# SCH_Plantcare_Module-v3_2024-10-31.net
KiCad netlist of a schematic drawn in EasyEDA
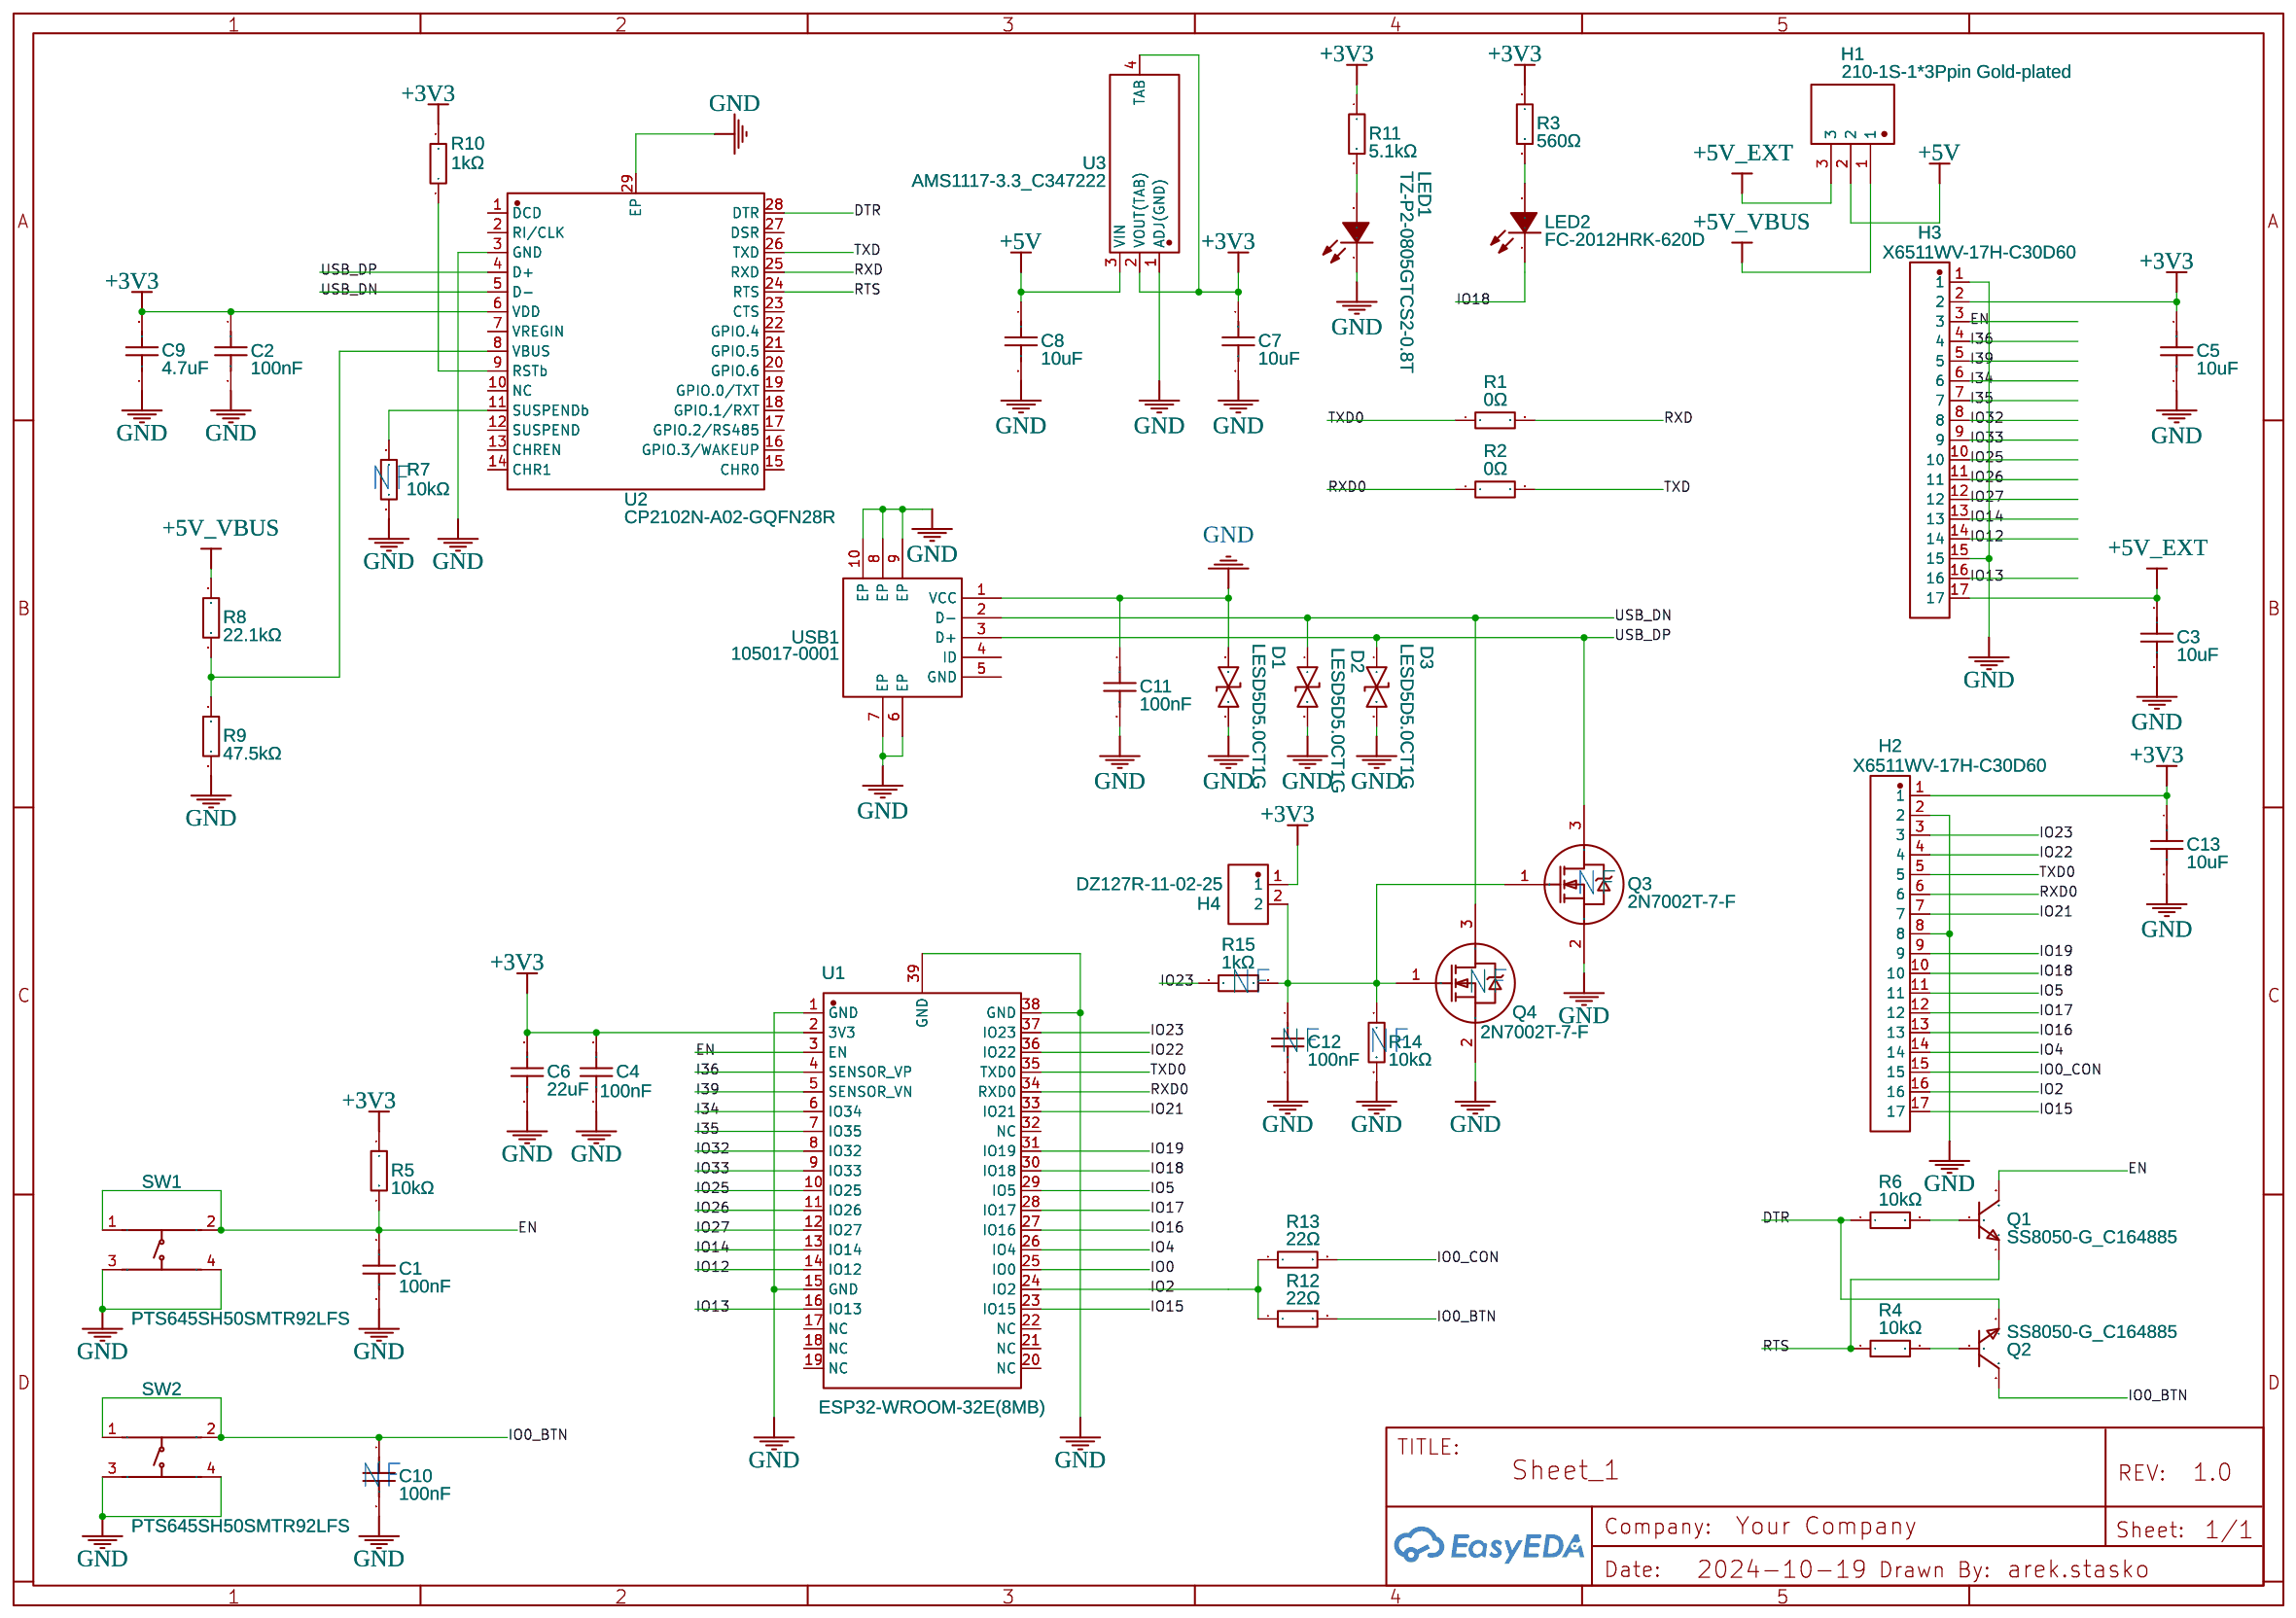
[diagram p0: schematic sheet]

(export (version "E")
  (design (tool "Eeschema 10.0.6"))
  (components
    (comp (ref "C1")
      (value "100nF")
      (fields
        (field (name "Manufacturer Part") "CL05B104KO5NNNC")
        (field (name "Manufacturer") "SAMSUNG(三星)")
      )
      (libsource (lib "") (part "CL05B104KO5NNNC"))
    )
    (comp (ref "C2")
      (value "100nF")
      (fields
        (field (name "Manufacturer Part") "CL05B104KO5NNNC")
        (field (name "Manufacturer") "SAMSUNG(三星)")
      )
      (libsource (lib "") (part "CL05B104KO5NNNC"))
    )
    (comp (ref "C3")
      (value "10uF")
      (fields
        (field (name "Manufacturer Part") "CL05A106MP5NUNC")
        (field (name "Manufacturer") "SAMSUNG(三星)")
      )
      (libsource (lib "") (part "CL05A106MP5NUNC_C315248"))
    )
    (comp (ref "C4")
      (value "100nF")
      (fields
        (field (name "Manufacturer Part") "CL05B104KO5NNNC")
        (field (name "Manufacturer") "SAMSUNG(三星)")
      )
      (libsource (lib "") (part "CL05B104KO5NNNC"))
    )
    (comp (ref "C5")
      (value "10uF")
      (fields
        (field (name "Manufacturer Part") "CL05A106MP5NUNC")
        (field (name "Manufacturer") "SAMSUNG(三星)")
      )
      (libsource (lib "") (part "CL05A106MP5NUNC_C315248"))
    )
    (comp (ref "C6")
      (value "22uF")
      (fields
        (field (name "Manufacturer Part") "CL21A226MAYNNNE")
        (field (name "Manufacturer") "SAMSUNG(三星)")
      )
      (libsource (lib "") (part "CL21A226MAYNNNE"))
    )
    (comp (ref "C7")
      (value "10uF")
      (fields
        (field (name "Manufacturer Part") "CL05A106MP5NUNC")
        (field (name "Manufacturer") "SAMSUNG(三星)")
      )
      (libsource (lib "") (part "CL05A106MP5NUNC_C315248"))
    )
    (comp (ref "C8")
      (value "10uF")
      (fields
        (field (name "Manufacturer Part") "CL05A106MP5NUNC")
        (field (name "Manufacturer") "SAMSUNG(三星)")
      )
      (libsource (lib "") (part "CL05A106MP5NUNC_C315248"))
    )
    (comp (ref "C9")
      (value "4.7uF")
      (fields
        (field (name "Manufacturer Part") "CL05A475KP5NRNC")
        (field (name "Manufacturer") "SAMSUNG(三星)")
      )
      (libsource (lib "") (part "CL05A475KP5NRNC"))
    )
    (comp (ref "C10")
      (value "100nF")
      (fields
        (field (name "Manufacturer Part") "CL05B104KO5NNNC")
        (field (name "Manufacturer") "SAMSUNG(三星)")
      )
      (libsource (lib "") (part "CL05B104KO5NNNC"))
    )
    (comp (ref "C11")
      (value "100nF")
      (fields
        (field (name "Manufacturer Part") "CL05B104KO5NNNC")
        (field (name "Manufacturer") "SAMSUNG(三星)")
      )
      (libsource (lib "") (part "CL05B104KO5NNNC"))
    )
    (comp (ref "C12")
      (value "100nF")
      (fields
        (field (name "Manufacturer Part") "CL05B104KO5NNNC")
        (field (name "Manufacturer") "SAMSUNG(三星)")
      )
      (libsource (lib "") (part "CL05B104KO5NNNC"))
    )
    (comp (ref "C13")
      (value "10uF")
      (fields
        (field (name "Manufacturer Part") "CL05A106MP5NUNC")
        (field (name "Manufacturer") "SAMSUNG(三星)")
      )
      (libsource (lib "") (part "CL05A106MP5NUNC_C315248"))
    )
    (comp (ref "D1")
      (value "LESD5D5.0CT1G")
      (fields (field (name "Manufacturer") "LRC(乐山无线电)"))
      (libsource (lib "") (part "LESD5D5.0CT1G"))
    )
    (comp (ref "D2")
      (value "LESD5D5.0CT1G")
      (fields (field (name "Manufacturer") "LRC(乐山无线电)"))
      (libsource (lib "") (part "LESD5D5.0CT1G_1"))
    )
    (comp (ref "D3")
      (value "LESD5D5.0CT1G")
      (fields (field (name "Manufacturer") "LRC(乐山无线电)"))
      (libsource (lib "") (part "LESD5D5.0CT1G_1"))
    )
    (comp (ref "H1")
      (value "210-1S-1*3Ppin Gold-plated")
      (fields (field (name "Manufacturer Part") "B-2101S03P-A110") (field (name "Manufacturer") "Ckmtw(灿科盟)"))
      (libsource (lib "") (part "210-1S-1*3Ppin Gold-plated"))
    )
    (comp (ref "H2")
      (value "X6511WV-17H-C30D60")
      (fields
        (field (name "Manufacturer Part") "X6511WV-17H-C60D30")
        (field (name "Manufacturer") "XKB Connection(中国星坤)")
      )
      (libsource (lib "") (part "X6511WV-17H-C30D60"))
    )
    (comp (ref "H3")
      (value "X6511WV-17H-C30D60")
      (fields
        (field (name "Manufacturer Part") "X6511WV-17H-C60D30")
        (field (name "Manufacturer") "XKB Connection(中国星坤)")
      )
      (libsource (lib "") (part "X6511WV-17H-C30D60"))
    )
    (comp (ref "H4")
      (value "DZ127R-11-02-25")
      (fields (field (name "Manufacturer") "DEALON(德艺隆)"))
      (libsource (lib "") (part "DZ127R-11-02-25"))
    )
    (comp (ref "LED1")
      (value "TZ-P2-0805GTCS2-0.8T")
      (fields (field (name "Manufacturer") "TUOZHAN(拓展光电)"))
      (libsource (lib "") (part "TZ-P2-0805GTCS2-0.8T"))
    )
    (comp (ref "LED2")
      (value "FC-2012HRK-620D")
      (fields (field (name "Manufacturer Part") "NCD0805R1") (field (name "Manufacturer") "国星光电"))
      (libsource (lib "") (part "FC-2012HRK-620D"))
    )
    (comp (ref "Q1")
      (value "SS8050-G_C164885")
      (fields (field (name "Manufacturer Part") "SS8050-G") (field (name "Manufacturer") "CJ(江苏长电/长晶)"))
      (libsource (lib "") (part "SS8050-G_C164885_1"))
    )
    (comp (ref "Q2")
      (value "SS8050-G_C164885")
      (fields (field (name "Manufacturer Part") "SS8050-G") (field (name "Manufacturer") "CJ(江苏长电/长晶)"))
      (libsource (lib "") (part "SS8050-G_C164885"))
    )
    (comp (ref "Q3")
      (value "2N7002T-7-F")
      (fields (field (name "Manufacturer") "DIODES(美台)"))
      (libsource (lib "") (part "2N7002T-7-F"))
    )
    (comp (ref "Q4")
      (value "2N7002T-7-F")
      (fields (field (name "Manufacturer") "DIODES(美台)"))
      (libsource (lib "") (part "2N7002T-7-F"))
    )
    (comp (ref "R1")
      (value "0Ω")
      (fields
        (field (name "Manufacturer Part") "0402WGF0000TCE")
        (field (name "Manufacturer") "UNI-ROYAL(厚声)")
      )
      (libsource (lib "") (part "0402WGF0000TCE"))
    )
    (comp (ref "R2")
      (value "0Ω")
      (fields
        (field (name "Manufacturer Part") "0402WGF0000TCE")
        (field (name "Manufacturer") "UNI-ROYAL(厚声)")
      )
      (libsource (lib "") (part "0402WGF0000TCE"))
    )
    (comp (ref "R3")
      (value "560Ω")
      (fields
        (field (name "Manufacturer Part") "0402WGF5600TCE")
        (field (name "Manufacturer") "UNI-ROYAL(厚声)")
      )
      (libsource (lib "") (part "0402WGF5600TCE"))
    )
    (comp (ref "R4")
      (value "10kΩ")
      (fields
        (field (name "Manufacturer Part") "0402WGF1002TCE")
        (field (name "Manufacturer") "UNI-ROYAL(厚声)")
      )
      (libsource (lib "") (part "0402WGF1002TCE"))
    )
    (comp (ref "R5")
      (value "10kΩ")
      (fields
        (field (name "Manufacturer Part") "0402WGF1002TCE")
        (field (name "Manufacturer") "UNI-ROYAL(厚声)")
      )
      (libsource (lib "") (part "0402WGF1002TCE_1"))
    )
    (comp (ref "R6")
      (value "10kΩ")
      (fields
        (field (name "Manufacturer Part") "0402WGF1002TCE")
        (field (name "Manufacturer") "UNI-ROYAL(厚声)")
      )
      (libsource (lib "") (part "0402WGF1002TCE"))
    )
    (comp (ref "R7")
      (value "10kΩ")
      (fields
        (field (name "Manufacturer Part") "0402WGF1002TCE")
        (field (name "Manufacturer") "UNI-ROYAL(厚声)")
      )
      (libsource (lib "") (part "0402WGF1002TCE_1"))
    )
    (comp (ref "R8")
      (value "22.1kΩ")
      (fields
        (field (name "Manufacturer Part") "0402WGF2212TCE")
        (field (name "Manufacturer") "UNI-ROYAL(厚声)")
      )
      (libsource (lib "") (part "0402WGF2212TCE"))
    )
    (comp (ref "R9")
      (value "47.5kΩ")
      (fields
        (field (name "Manufacturer Part") "0402WGF4752TCE")
        (field (name "Manufacturer") "UNI-ROYAL(厚声)")
      )
      (libsource (lib "") (part "0402WGF4752TCE"))
    )
    (comp (ref "R10")
      (value "1kΩ")
      (fields
        (field (name "Manufacturer Part") "0402WGF1001TCE")
        (field (name "Manufacturer") "UNI-ROYAL(厚声)")
      )
      (libsource (lib "") (part "0402WGF1001TCE"))
    )
    (comp (ref "R11")
      (value "5.1kΩ")
      (fields
        (field (name "Manufacturer Part") "0402WGF5101TCE")
        (field (name "Manufacturer") "UNI-ROYAL(厚声)")
      )
      (libsource (lib "") (part "0402WGF5101TCE"))
    )
    (comp (ref "R12")
      (value "22Ω")
      (fields
        (field (name "Manufacturer Part") "0402WGF220JTCE")
        (field (name "Manufacturer") "UNI-ROYAL(厚声)")
      )
      (libsource (lib "") (part "0402WGF220JTCE"))
    )
    (comp (ref "R13")
      (value "22Ω")
      (fields
        (field (name "Manufacturer Part") "0402WGF220JTCE")
        (field (name "Manufacturer") "UNI-ROYAL(厚声)")
      )
      (libsource (lib "") (part "0402WGF220JTCE"))
    )
    (comp (ref "R14")
      (value "10kΩ")
      (fields
        (field (name "Manufacturer Part") "0402WGF1002TCE")
        (field (name "Manufacturer") "UNI-ROYAL(厚声)")
      )
      (libsource (lib "") (part "0402WGF1002TCE_1"))
    )
    (comp (ref "R15")
      (value "1kΩ")
      (fields
        (field (name "Manufacturer Part") "0402WGF1001TCE")
        (field (name "Manufacturer") "UNI-ROYAL(厚声)")
      )
      (libsource (lib "") (part "0402WGF1001TCE_1"))
    )
    (comp (ref "SW1")
      (value "PTS645SH50SMTR92LFS")
      (fields (field (name "Manufacturer") "C&K"))
      (libsource (lib "") (part "PTS645SH50SMTR92LFS"))
    )
    (comp (ref "SW2")
      (value "PTS645SH50SMTR92LFS")
      (fields (field (name "Manufacturer") "C&K"))
      (libsource (lib "") (part "PTS645SH50SMTR92LFS"))
    )
    (comp (ref "U1")
      (value "ESP32-WROOM-32E(8MB)")
      (fields
        (field (name "Manufacturer Part") "ESP32-WROOM-32E-N8")
        (field (name "Manufacturer") "ESPRESSIF(乐鑫)")
      )
      (libsource (lib "") (part "ESP32-WROOM-32E(8MB)"))
    )
    (comp (ref "U2")
      (value "CP2102N-A02-GQFN28R")
      (fields (field (name "Manufacturer") "SKYWORKS/SILICON LABS(芯科)"))
      (libsource (lib "") (part "CP2102N-A02-GQFN28R"))
    )
    (comp (ref "U3")
      (value "AMS1117-3.3_C347222")
      (fields (field (name "Manufacturer Part") "AMS1117-3.3") (field (name "Manufacturer") "UMW(友台半导体)"))
      (libsource (lib "") (part "AMS1117-3.3_C347222"))
    )
    (comp (ref "USB1")
      (value "105017-0001")
      (fields (field (name "Manufacturer Part") "1050170001") (field (name "Manufacturer") "MOLEX"))
      (libsource (lib "") (part "105017-0001"))
    )
  )
  (nets
    (net (code "1") (name "+3V3") (class "Default")
      (node (ref "C13") (pin "1") (pinfunction "1_1") (pintype "unspecified"))
      (node (ref "C2") (pin "1") (pinfunction "1_1") (pintype "unspecified"))
      (node (ref "C4") (pin "1") (pinfunction "1_1") (pintype "unspecified"))
      (node (ref "C5") (pin "1") (pinfunction "1_1") (pintype "unspecified"))
      (node (ref "C6") (pin "1") (pinfunction "1_1") (pintype "unspecified"))
      (node (ref "C7") (pin "1") (pinfunction "1_1") (pintype "unspecified"))
      (node (ref "C9") (pin "2") (pinfunction "2_2") (pintype "unspecified"))
      (node (ref "H2") (pin "1") (pinfunction "1_1") (pintype "unspecified"))
      (node (ref "H3") (pin "2") (pinfunction "2_2") (pintype "unspecified"))
      (node (ref "H4") (pin "1") (pinfunction "1_1") (pintype "unspecified"))
      (node (ref "R10") (pin "2") (pinfunction "2_2") (pintype "input"))
      (node (ref "R11") (pin "1") (pinfunction "1_1") (pintype "input"))
      (node (ref "R3") (pin "1") (pinfunction "1_1") (pintype "input"))
      (node (ref "R5") (pin "1") (pinfunction "1_1") (pintype "input"))
      (node (ref "U1") (pin "2") (pinfunction "3V3_2") (pintype "unspecified"))
      (node (ref "U2") (pin "6") (pinfunction "VDD_6") (pintype "unspecified"))
      (node (ref "U3") (pin "2") (pinfunction "VOUT(TAB)_2") (pintype "unspecified"))
      (node (ref "U3") (pin "4") (pinfunction "TAB_4") (pintype "unspecified"))
    )
    (net (code "2") (name "+5V") (class "Default")
      (node (ref "C8") (pin "1") (pinfunction "1_1") (pintype "unspecified"))
      (node (ref "H1") (pin "2") (pinfunction "2_2") (pintype "unspecified"))
      (node (ref "U3") (pin "3") (pinfunction "VIN_3") (pintype "unspecified"))
    )
    (net (code "3") (name "+5V_EXT") (class "Default")
      (node (ref "C3") (pin "1") (pinfunction "1_1") (pintype "unspecified"))
      (node (ref "H1") (pin "3") (pinfunction "3_3") (pintype "unspecified"))
      (node (ref "H3") (pin "17") (pinfunction "17_17") (pintype "unspecified"))
    )
    (net (code "4") (name "+5V_VBUS") (class "Default")
      (node (ref "H1") (pin "1") (pinfunction "1_1") (pintype "unspecified"))
      (node (ref "R8") (pin "1") (pinfunction "1_1") (pintype "input"))
    )
    (net (code "5") (name "/DTR") (class "Default")
      (node (ref "Q2") (pin "2") (pinfunction "E_2") (pintype "unspecified"))
      (node (ref "R6") (pin "1") (pinfunction "1_1") (pintype "input"))
      (node (ref "U2") (pin "28") (pinfunction "DTR_28") (pintype "unspecified"))
    )
    (net (code "6") (name "/EN") (class "Default")
      (node (ref "C1") (pin "1") (pinfunction "1_1") (pintype "unspecified"))
      (node (ref "H3") (pin "3") (pinfunction "3_3") (pintype "unspecified"))
      (node (ref "Q1") (pin "3") (pinfunction "C_3") (pintype "unspecified"))
      (node (ref "R5") (pin "2") (pinfunction "2_2") (pintype "input"))
      (node (ref "SW1") (pin "1") (pinfunction "1_1") (pintype "unspecified"))
      (node (ref "SW1") (pin "2") (pinfunction "2_2") (pintype "unspecified"))
      (node (ref "U1") (pin "3") (pinfunction "EN_3") (pintype "unspecified"))
    )
    (net (code "7") (name "/I34") (class "Default")
      (node (ref "H3") (pin "6") (pinfunction "6_6") (pintype "unspecified"))
      (node (ref "U1") (pin "6") (pinfunction "IO34_6") (pintype "unspecified"))
    )
    (net (code "8") (name "/I35") (class "Default")
      (node (ref "H3") (pin "7") (pinfunction "7_7") (pintype "unspecified"))
      (node (ref "U1") (pin "7") (pinfunction "IO35_7") (pintype "unspecified"))
    )
    (net (code "9") (name "/I36") (class "Default")
      (node (ref "H3") (pin "4") (pinfunction "4_4") (pintype "unspecified"))
      (node (ref "U1") (pin "4") (pinfunction "SENSOR_VP_4") (pintype "unspecified"))
    )
    (net (code "10") (name "/I39") (class "Default")
      (node (ref "H3") (pin "5") (pinfunction "5_5") (pintype "unspecified"))
      (node (ref "U1") (pin "5") (pinfunction "SENSOR_VN_5") (pintype "unspecified"))
    )
    (net (code "11") (name "/IO0") (class "Default")
      (node (ref "U1") (pin "25") (pinfunction "IO0_25") (pintype "unspecified"))
    )
    (net (code "12") (name "/IO0_BTN") (class "Default")
      (node (ref "C10") (pin "1") (pinfunction "1_1") (pintype "unspecified"))
      (node (ref "Q2") (pin "3") (pinfunction "C_3") (pintype "unspecified"))
      (node (ref "R12") (pin "2") (pinfunction "2_2") (pintype "input"))
      (node (ref "SW2") (pin "1") (pinfunction "1_1") (pintype "unspecified"))
      (node (ref "SW2") (pin "2") (pinfunction "2_2") (pintype "unspecified"))
    )
    (net (code "13") (name "/IO0_CON") (class "Default")
      (node (ref "H2") (pin "15") (pinfunction "15_15") (pintype "unspecified"))
      (node (ref "R13") (pin "2") (pinfunction "2_2") (pintype "input"))
    )
    (net (code "14") (name "/IO2") (class "Default")
      (node (ref "H2") (pin "16") (pinfunction "16_16") (pintype "unspecified"))
      (node (ref "R12") (pin "1") (pinfunction "1_1") (pintype "input"))
      (node (ref "R13") (pin "1") (pinfunction "1_1") (pintype "input"))
      (node (ref "U1") (pin "24") (pinfunction "IO2_24") (pintype "unspecified"))
    )
    (net (code "15") (name "/IO4") (class "Default")
      (node (ref "H2") (pin "14") (pinfunction "14_14") (pintype "unspecified"))
      (node (ref "U1") (pin "26") (pinfunction "IO4_26") (pintype "unspecified"))
    )
    (net (code "16") (name "/IO5") (class "Default")
      (node (ref "H2") (pin "11") (pinfunction "11_11") (pintype "unspecified"))
      (node (ref "U1") (pin "29") (pinfunction "IO5_29") (pintype "unspecified"))
    )
    (net (code "17") (name "/IO12") (class "Default")
      (node (ref "H3") (pin "14") (pinfunction "14_14") (pintype "unspecified"))
      (node (ref "U1") (pin "14") (pinfunction "IO12_14") (pintype "unspecified"))
    )
    (net (code "18") (name "/IO13") (class "Default")
      (node (ref "H3") (pin "16") (pinfunction "16_16") (pintype "unspecified"))
      (node (ref "U1") (pin "16") (pinfunction "IO13_16") (pintype "unspecified"))
    )
    (net (code "19") (name "/IO14") (class "Default")
      (node (ref "H3") (pin "13") (pinfunction "13_13") (pintype "unspecified"))
      (node (ref "U1") (pin "13") (pinfunction "IO14_13") (pintype "unspecified"))
    )
    (net (code "20") (name "/IO15") (class "Default")
      (node (ref "H2") (pin "17") (pinfunction "17_17") (pintype "unspecified"))
      (node (ref "U1") (pin "23") (pinfunction "IO15_23") (pintype "unspecified"))
    )
    (net (code "21") (name "/IO16") (class "Default")
      (node (ref "H2") (pin "13") (pinfunction "13_13") (pintype "unspecified"))
      (node (ref "U1") (pin "27") (pinfunction "IO16_27") (pintype "unspecified"))
    )
    (net (code "22") (name "/IO17") (class "Default")
      (node (ref "H2") (pin "12") (pinfunction "12_12") (pintype "unspecified"))
      (node (ref "U1") (pin "28") (pinfunction "IO17_28") (pintype "unspecified"))
    )
    (net (code "23") (name "/IO18") (class "Default")
      (node (ref "H2") (pin "10") (pinfunction "10_10") (pintype "unspecified"))
      (node (ref "LED2") (pin "2") (pinfunction "-_2") (pintype "unspecified"))
      (node (ref "U1") (pin "30") (pinfunction "IO18_30") (pintype "unspecified"))
    )
    (net (code "24") (name "/IO19") (class "Default")
      (node (ref "H2") (pin "9") (pinfunction "9_9") (pintype "unspecified"))
      (node (ref "U1") (pin "31") (pinfunction "IO19_31") (pintype "unspecified"))
    )
    (net (code "25") (name "/IO21") (class "Default")
      (node (ref "H2") (pin "7") (pinfunction "7_7") (pintype "unspecified"))
      (node (ref "U1") (pin "33") (pinfunction "IO21_33") (pintype "unspecified"))
    )
    (net (code "26") (name "/IO22") (class "Default")
      (node (ref "H2") (pin "4") (pinfunction "4_4") (pintype "unspecified"))
      (node (ref "U1") (pin "36") (pinfunction "IO22_36") (pintype "unspecified"))
    )
    (net (code "27") (name "/IO23") (class "Default")
      (node (ref "H2") (pin "3") (pinfunction "3_3") (pintype "unspecified"))
      (node (ref "R15") (pin "1") (pinfunction "1_1") (pintype "input"))
      (node (ref "U1") (pin "37") (pinfunction "IO23_37") (pintype "unspecified"))
    )
    (net (code "28") (name "/IO25") (class "Default")
      (node (ref "H3") (pin "10") (pinfunction "10_10") (pintype "unspecified"))
      (node (ref "U1") (pin "10") (pinfunction "IO25_10") (pintype "unspecified"))
    )
    (net (code "29") (name "/IO26") (class "Default")
      (node (ref "H3") (pin "11") (pinfunction "11_11") (pintype "unspecified"))
      (node (ref "U1") (pin "11") (pinfunction "IO26_11") (pintype "unspecified"))
    )
    (net (code "30") (name "/IO27") (class "Default")
      (node (ref "H3") (pin "12") (pinfunction "12_12") (pintype "unspecified"))
      (node (ref "U1") (pin "12") (pinfunction "IO27_12") (pintype "unspecified"))
    )
    (net (code "31") (name "/IO32") (class "Default")
      (node (ref "H3") (pin "8") (pinfunction "8_8") (pintype "unspecified"))
      (node (ref "U1") (pin "8") (pinfunction "IO32_8") (pintype "unspecified"))
    )
    (net (code "32") (name "/IO33") (class "Default")
      (node (ref "H3") (pin "9") (pinfunction "9_9") (pintype "unspecified"))
      (node (ref "U1") (pin "9") (pinfunction "IO33_9") (pintype "unspecified"))
    )
    (net (code "33") (name "/RTS") (class "Default")
      (node (ref "Q1") (pin "2") (pinfunction "E_2") (pintype "unspecified"))
      (node (ref "R4") (pin "1") (pinfunction "1_1") (pintype "input"))
      (node (ref "U2") (pin "24") (pinfunction "RTS_24") (pintype "unspecified"))
    )
    (net (code "34") (name "/RXD") (class "Default")
      (node (ref "R1") (pin "2") (pinfunction "2_2") (pintype "input"))
      (node (ref "U2") (pin "25") (pinfunction "RXD_25") (pintype "unspecified"))
    )
    (net (code "35") (name "/RXD0") (class "Default")
      (node (ref "H2") (pin "6") (pinfunction "6_6") (pintype "unspecified"))
      (node (ref "R2") (pin "1") (pinfunction "1_1") (pintype "input"))
      (node (ref "U1") (pin "34") (pinfunction "RXD0_34") (pintype "unspecified"))
    )
    (net (code "36") (name "/TXD") (class "Default")
      (node (ref "R2") (pin "2") (pinfunction "2_2") (pintype "input"))
      (node (ref "U2") (pin "26") (pinfunction "TXD_26") (pintype "unspecified"))
    )
    (net (code "37") (name "/TXD0") (class "Default")
      (node (ref "H2") (pin "5") (pinfunction "5_5") (pintype "unspecified"))
      (node (ref "R1") (pin "1") (pinfunction "1_1") (pintype "input"))
      (node (ref "U1") (pin "35") (pinfunction "TXD0_35") (pintype "unspecified"))
    )
    (net (code "38") (name "/USB_DN") (class "Default")
      (node (ref "D2") (pin "1") (pinfunction "1_1") (pintype "unspecified"))
      (node (ref "Q4") (pin "3") (pinfunction "D_3") (pintype "unspecified"))
      (node (ref "U2") (pin "5") (pinfunction "D-_5") (pintype "unspecified"))
      (node (ref "USB1") (pin "2") (pinfunction "D-_2") (pintype "unspecified"))
    )
    (net (code "39") (name "/USB_DP") (class "Default")
      (node (ref "D3") (pin "1") (pinfunction "1_1") (pintype "unspecified"))
      (node (ref "Q3") (pin "3") (pinfunction "D_3") (pintype "unspecified"))
      (node (ref "U2") (pin "4") (pinfunction "D+_4") (pintype "unspecified"))
      (node (ref "USB1") (pin "3") (pinfunction "D+_3") (pintype "unspecified"))
    )
    (net (code "40") (name "GND") (class "Default")
      (node (ref "C1") (pin "2") (pinfunction "2_2") (pintype "unspecified"))
      (node (ref "C10") (pin "2") (pinfunction "2_2") (pintype "unspecified"))
      (node (ref "C11") (pin "1") (pinfunction "1_1") (pintype "unspecified"))
      (node (ref "C11") (pin "2") (pinfunction "2_2") (pintype "unspecified"))
      (node (ref "C12") (pin "2") (pinfunction "2_2") (pintype "unspecified"))
      (node (ref "C13") (pin "2") (pinfunction "2_2") (pintype "unspecified"))
      (node (ref "C2") (pin "2") (pinfunction "2_2") (pintype "unspecified"))
      (node (ref "C3") (pin "2") (pinfunction "2_2") (pintype "unspecified"))
      (node (ref "C4") (pin "2") (pinfunction "2_2") (pintype "unspecified"))
      (node (ref "C5") (pin "2") (pinfunction "2_2") (pintype "unspecified"))
      (node (ref "C6") (pin "2") (pinfunction "2_2") (pintype "unspecified"))
      (node (ref "C7") (pin "2") (pinfunction "2_2") (pintype "unspecified"))
      (node (ref "C8") (pin "2") (pinfunction "2_2") (pintype "unspecified"))
      (node (ref "C9") (pin "1") (pinfunction "1_1") (pintype "unspecified"))
      (node (ref "D1") (pin "1") (pinfunction "1_1") (pintype "unspecified"))
      (node (ref "D1") (pin "2") (pinfunction "2_2") (pintype "unspecified"))
      (node (ref "D2") (pin "2") (pinfunction "2_2") (pintype "unspecified"))
      (node (ref "D3") (pin "2") (pinfunction "2_2") (pintype "unspecified"))
      (node (ref "H2") (pin "2") (pinfunction "2_2") (pintype "unspecified"))
      (node (ref "H2") (pin "8") (pinfunction "8_8") (pintype "unspecified"))
      (node (ref "H3") (pin "1") (pinfunction "1_1") (pintype "unspecified"))
      (node (ref "H3") (pin "15") (pinfunction "15_15") (pintype "unspecified"))
      (node (ref "LED1") (pin "1") (pinfunction "-_1") (pintype "unspecified"))
      (node (ref "Q3") (pin "2") (pinfunction "S_2") (pintype "unspecified"))
      (node (ref "Q4") (pin "2") (pinfunction "S_2") (pintype "unspecified"))
      (node (ref "R14") (pin "2") (pinfunction "2_2") (pintype "input"))
      (node (ref "R7") (pin "2") (pinfunction "2_2") (pintype "input"))
      (node (ref "R9") (pin "2") (pinfunction "2_2") (pintype "input"))
      (node (ref "SW1") (pin "3") (pinfunction "3_3") (pintype "unspecified"))
      (node (ref "SW1") (pin "4") (pinfunction "4_4") (pintype "unspecified"))
      (node (ref "SW2") (pin "3") (pinfunction "3_3") (pintype "unspecified"))
      (node (ref "SW2") (pin "4") (pinfunction "4_4") (pintype "unspecified"))
      (node (ref "U1") (pin "1") (pinfunction "GND_1") (pintype "unspecified"))
      (node (ref "U1") (pin "15") (pinfunction "GND_15") (pintype "unspecified"))
      (node (ref "U1") (pin "38") (pinfunction "GND_38") (pintype "unspecified"))
      (node (ref "U1") (pin "39") (pinfunction "GND_39") (pintype "unspecified"))
      (node (ref "U2") (pin "29") (pinfunction "EP_29") (pintype "unspecified"))
      (node (ref "U2") (pin "3") (pinfunction "GND_3") (pintype "unspecified"))
      (node (ref "U3") (pin "1") (pinfunction "ADJ(GND)_1") (pintype "unspecified"))
      (node (ref "USB1") (pin "1") (pinfunction "VCC_1") (pintype "unspecified"))
      (node (ref "USB1") (pin "10") (pinfunction "EP_10") (pintype "unspecified"))
      (node (ref "USB1") (pin "6") (pinfunction "EP_6") (pintype "unspecified"))
      (node (ref "USB1") (pin "7") (pinfunction "EP_7") (pintype "unspecified"))
      (node (ref "USB1") (pin "8") (pinfunction "EP_8") (pintype "unspecified"))
      (node (ref "USB1") (pin "9") (pinfunction "EP_9") (pintype "unspecified"))
    )
    (net (code "41") (name "Net-(LED1-+)") (class "Default")
      (node (ref "LED1") (pin "2") (pinfunction "+_2") (pintype "unspecified"))
      (node (ref "R11") (pin "2") (pinfunction "2_2") (pintype "input"))
    )
    (net (code "42") (name "Net-(LED2-+)") (class "Default")
      (node (ref "LED2") (pin "1") (pinfunction "+_1") (pintype "unspecified"))
      (node (ref "R3") (pin "2") (pinfunction "2_2") (pintype "input"))
    )
    (net (code "43") (name "Net-(Q1-B)") (class "Default")
      (node (ref "Q1") (pin "1") (pinfunction "B_1") (pintype "unspecified"))
      (node (ref "R6") (pin "2") (pinfunction "2_2") (pintype "input"))
    )
    (net (code "44") (name "Net-(Q2-B)") (class "Default")
      (node (ref "Q2") (pin "1") (pinfunction "B_1") (pintype "unspecified"))
      (node (ref "R4") (pin "2") (pinfunction "2_2") (pintype "input"))
    )
    (net (code "45") (name "Net-(Q3-G)") (class "Default")
      (node (ref "C12") (pin "1") (pinfunction "1_1") (pintype "unspecified"))
      (node (ref "H4") (pin "2") (pinfunction "2_2") (pintype "unspecified"))
      (node (ref "Q3") (pin "1") (pinfunction "G_1") (pintype "unspecified"))
      (node (ref "Q4") (pin "1") (pinfunction "G_1") (pintype "unspecified"))
      (node (ref "R14") (pin "1") (pinfunction "1_1") (pintype "input"))
      (node (ref "R15") (pin "2") (pinfunction "2_2") (pintype "input"))
    )
    (net (code "46") (name "Net-(U2-RSTb)") (class "Default")
      (node (ref "R10") (pin "1") (pinfunction "1_1") (pintype "input"))
      (node (ref "U2") (pin "9") (pinfunction "RSTb_9") (pintype "unspecified"))
    )
    (net (code "47") (name "Net-(U2-SUSPENDb)") (class "Default")
      (node (ref "R7") (pin "1") (pinfunction "1_1") (pintype "input"))
      (node (ref "U2") (pin "11") (pinfunction "SUSPENDb_11") (pintype "unspecified"))
    )
    (net (code "48") (name "Net-(U2-VBUS)") (class "Default")
      (node (ref "R8") (pin "2") (pinfunction "2_2") (pintype "input"))
      (node (ref "R9") (pin "1") (pinfunction "1_1") (pintype "input"))
      (node (ref "U2") (pin "8") (pinfunction "VBUS_8") (pintype "unspecified"))
    )
    (net (code "49") (name "unconnected-(U1-NC-Pad17)") (class "Default")
      (node (ref "U1") (pin "17") (pinfunction "NC_17") (pintype "unspecified"))
    )
    (net (code "50") (name "unconnected-(U1-NC-Pad18)") (class "Default")
      (node (ref "U1") (pin "18") (pinfunction "NC_18") (pintype "unspecified"))
    )
    (net (code "51") (name "unconnected-(U1-NC-Pad19)") (class "Default")
      (node (ref "U1") (pin "19") (pinfunction "NC_19") (pintype "unspecified"))
    )
    (net (code "52") (name "unconnected-(U1-NC-Pad20)") (class "Default")
      (node (ref "U1") (pin "20") (pinfunction "NC_20") (pintype "unspecified"))
    )
    (net (code "53") (name "unconnected-(U1-NC-Pad21)") (class "Default")
      (node (ref "U1") (pin "21") (pinfunction "NC_21") (pintype "unspecified"))
    )
    (net (code "54") (name "unconnected-(U1-NC-Pad22)") (class "Default")
      (node (ref "U1") (pin "22") (pinfunction "NC_22") (pintype "unspecified"))
    )
    (net (code "55") (name "unconnected-(U1-NC-Pad32)") (class "Default")
      (node (ref "U1") (pin "32") (pinfunction "NC_32") (pintype "unspecified"))
    )
    (net (code "56") (name "unconnected-(U2-CHR0-Pad15)") (class "Default")
      (node (ref "U2") (pin "15") (pinfunction "CHR0_15") (pintype "unspecified"))
    )
    (net (code "57") (name "unconnected-(U2-CHR1-Pad14)") (class "Default")
      (node (ref "U2") (pin "14") (pinfunction "CHR1_14") (pintype "unspecified"))
    )
    (net (code "58") (name "unconnected-(U2-CHREN-Pad13)") (class "Default")
      (node (ref "U2") (pin "13") (pinfunction "CHREN_13") (pintype "unspecified"))
    )
    (net (code "59") (name "unconnected-(U2-CTS-Pad23)") (class "Default")
      (node (ref "U2") (pin "23") (pinfunction "CTS_23") (pintype "unspecified"))
    )
    (net (code "60") (name "unconnected-(U2-DCD-Pad1)") (class "Default")
      (node (ref "U2") (pin "1") (pinfunction "DCD_1") (pintype "unspecified"))
    )
    (net (code "61") (name "unconnected-(U2-DSR-Pad27)") (class "Default")
      (node (ref "U2") (pin "27") (pinfunction "DSR_27") (pintype "unspecified"))
    )
    (net (code "62") (name "unconnected-(U2-GPIO.0{slash}TXT-Pad19)") (class "Default")
      (node (ref "U2") (pin "19") (pinfunction "GPIO.0/TXT_19") (pintype "unspecified"))
    )
    (net (code "63") (name "unconnected-(U2-GPIO.1{slash}RXT-Pad18)") (class "Default")
      (node (ref "U2") (pin "18") (pinfunction "GPIO.1/RXT_18") (pintype "unspecified"))
    )
    (net (code "64") (name "unconnected-(U2-GPIO.2{slash}RS485-Pad17)") (class "Default")
      (node (ref "U2") (pin "17") (pinfunction "GPIO.2/RS485_17") (pintype "unspecified"))
    )
    (net (code "65") (name "unconnected-(U2-GPIO.3{slash}WAKEUP-Pad16)") (class "Default")
      (node (ref "U2") (pin "16") (pinfunction "GPIO.3/WAKEUP_16") (pintype "unspecified"))
    )
    (net (code "66") (name "unconnected-(U2-GPIO.4-Pad22)") (class "Default")
      (node (ref "U2") (pin "22") (pinfunction "GPIO.4_22") (pintype "unspecified"))
    )
    (net (code "67") (name "unconnected-(U2-GPIO.5-Pad21)") (class "Default")
      (node (ref "U2") (pin "21") (pinfunction "GPIO.5_21") (pintype "unspecified"))
    )
    (net (code "68") (name "unconnected-(U2-GPIO.6-Pad20)") (class "Default")
      (node (ref "U2") (pin "20") (pinfunction "GPIO.6_20") (pintype "unspecified"))
    )
    (net (code "69") (name "unconnected-(U2-NC-Pad10)") (class "Default")
      (node (ref "U2") (pin "10") (pinfunction "NC_10") (pintype "unspecified"))
    )
    (net (code "70") (name "unconnected-(U2-RI{slash}CLK-Pad2)") (class "Default")
      (node (ref "U2") (pin "2") (pinfunction "RI/CLK_2") (pintype "unspecified"))
    )
    (net (code "71") (name "unconnected-(U2-SUSPEND-Pad12)") (class "Default")
      (node (ref "U2") (pin "12") (pinfunction "SUSPEND_12") (pintype "unspecified"))
    )
    (net (code "72") (name "unconnected-(U2-VREGIN-Pad7)") (class "Default")
      (node (ref "U2") (pin "7") (pinfunction "VREGIN_7") (pintype "unspecified"))
    )
    (net (code "73") (name "unconnected-(USB1-GND-Pad5)") (class "Default")
      (node (ref "USB1") (pin "5") (pinfunction "GND_5") (pintype "unspecified"))
    )
    (net (code "74") (name "unconnected-(USB1-ID-Pad4)") (class "Default")
      (node (ref "USB1") (pin "4") (pinfunction "ID_4") (pintype "unspecified"))
    )
  )
)
